# DM3390_CAM_FFC_ESD_AUX.net
KiCad netlist of a schematic drawn in Altium Designer
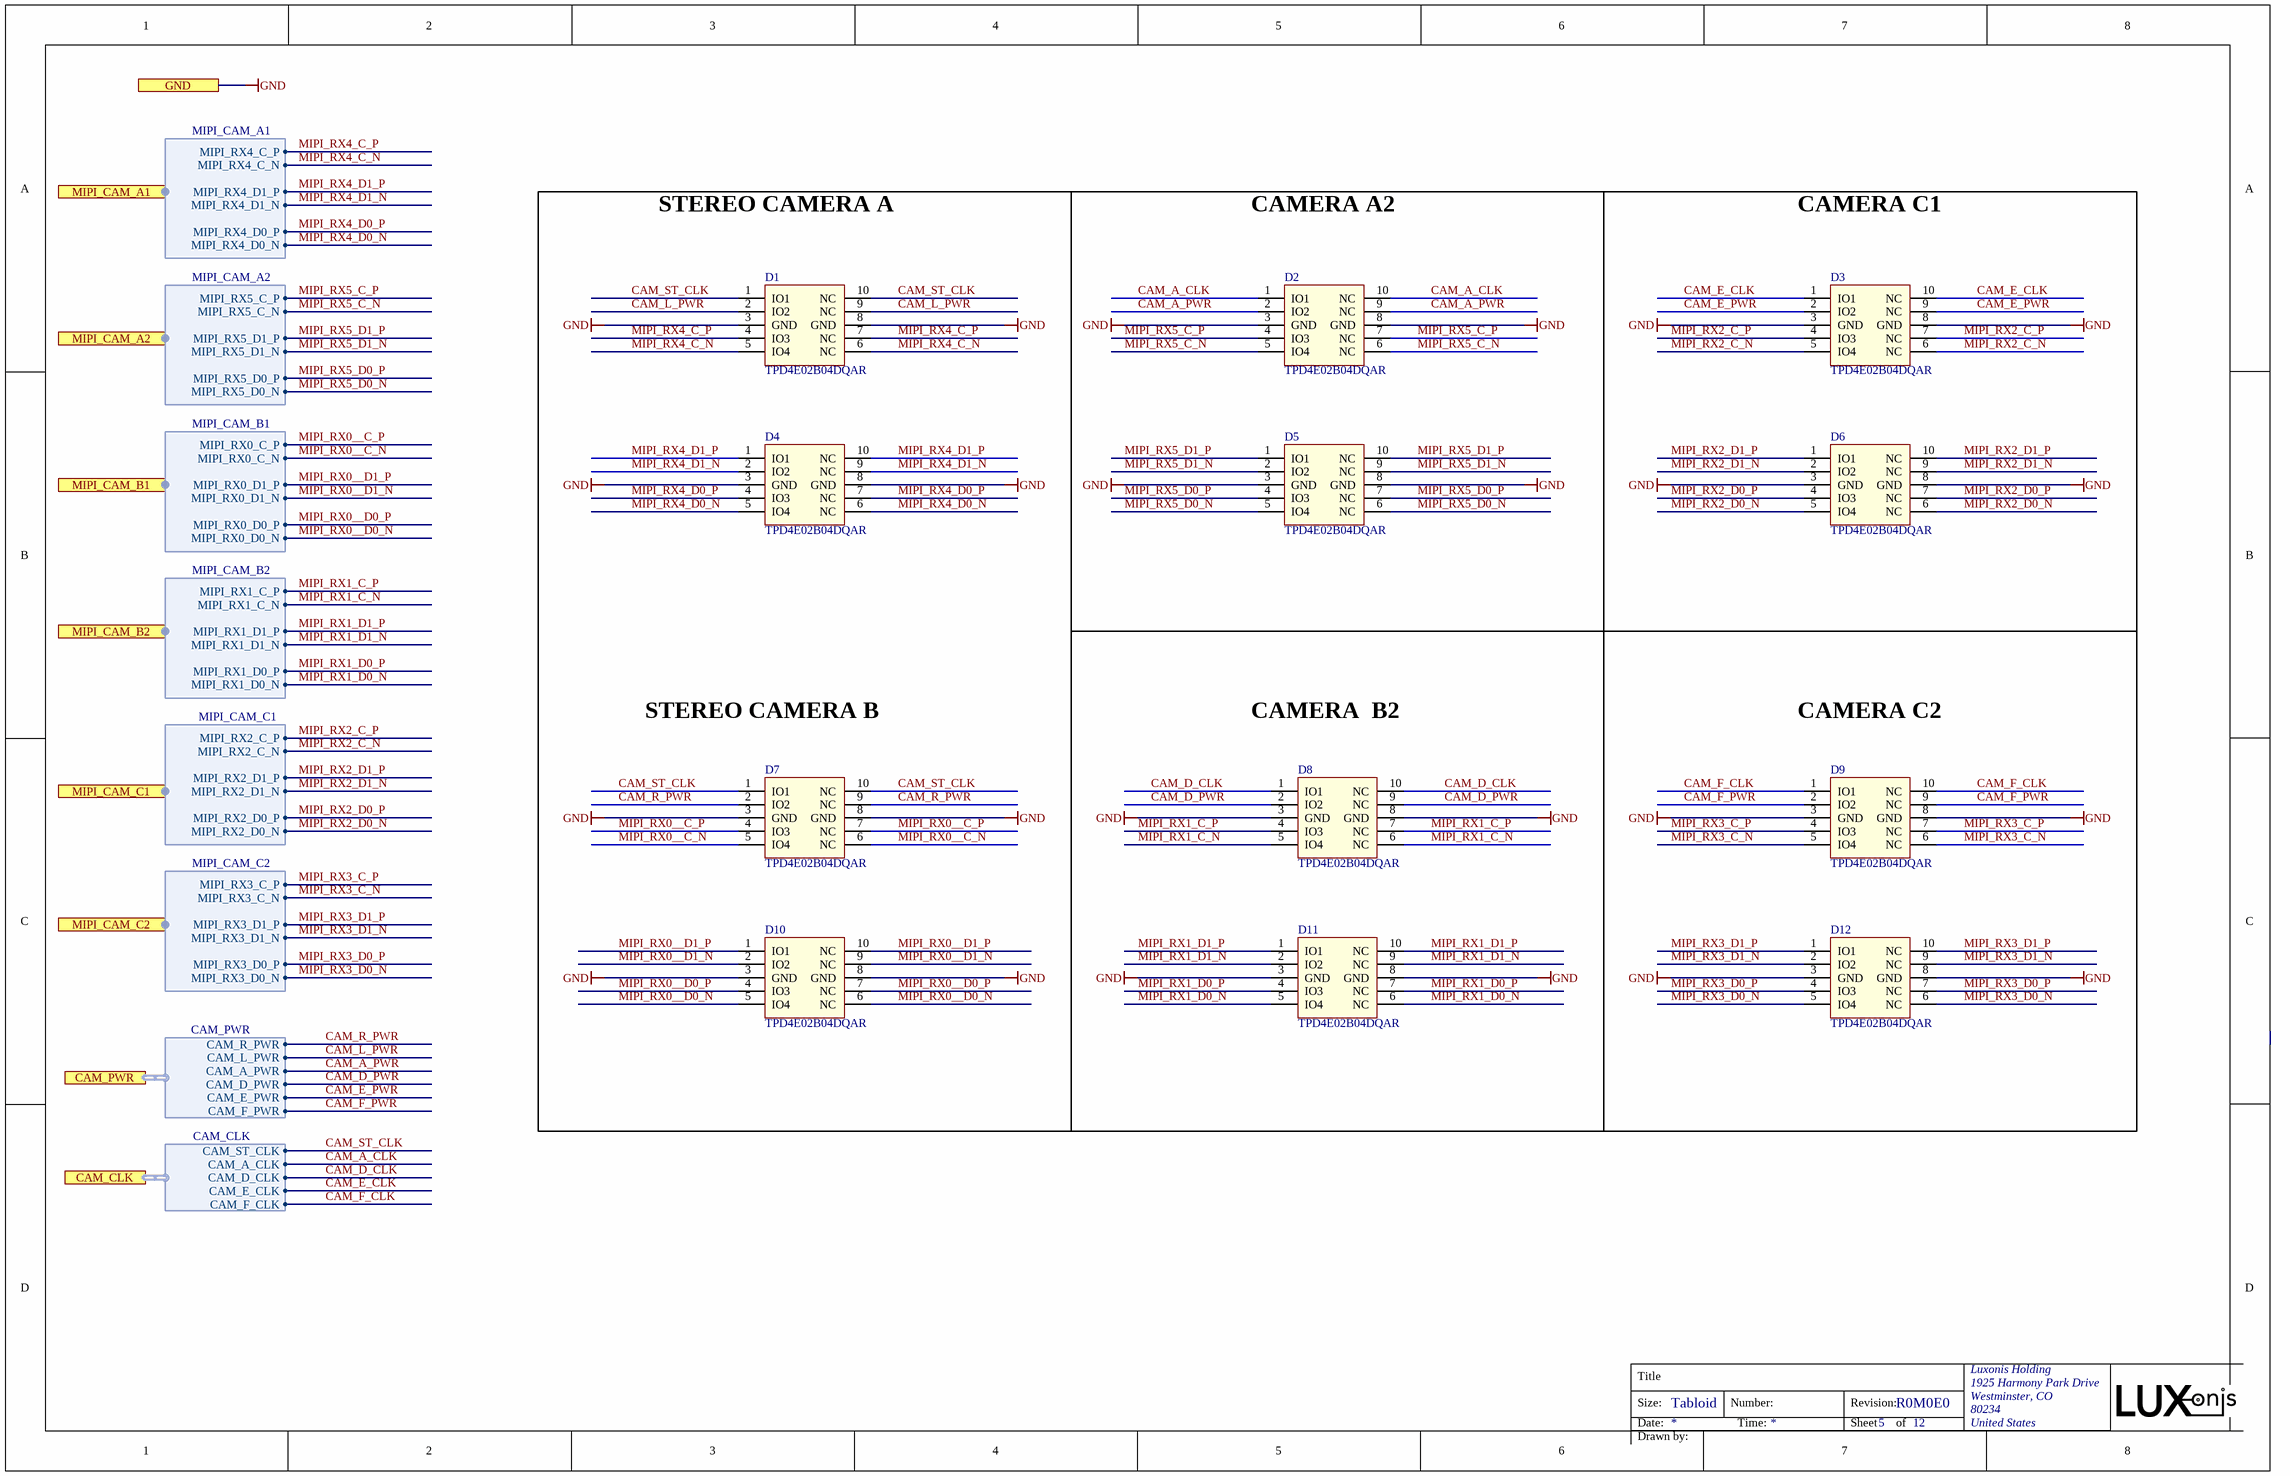
[diagram p0: DM3390_CAM_FFC_ESD_AUX.SchDoc]

(export (version "E")
  (design (tool "Eeschema 10.0.6"))
  (components
    (comp (ref "D1")
      (value "TPD4E02B04DQAR")
      (footprint "LuxonisMaster:TPD4E02B04DQAR")
      (libsource (lib "LuxonisMaster") (part "TPD4E02B04DQAR"))
    )
    (comp (ref "D2")
      (value "TPD4E02B04DQAR")
      (footprint "LuxonisMaster:TPD4E02B04DQAR")
      (libsource (lib "LuxonisMaster") (part "TPD4E02B04DQAR"))
    )
    (comp (ref "D3")
      (value "TPD4E02B04DQAR")
      (footprint "LuxonisMaster:TPD4E02B04DQAR")
      (libsource (lib "LuxonisMaster") (part "TPD4E02B04DQAR"))
    )
    (comp (ref "D4")
      (value "TPD4E02B04DQAR")
      (footprint "LuxonisMaster:TPD4E02B04DQAR")
      (libsource (lib "LuxonisMaster") (part "TPD4E02B04DQAR"))
    )
    (comp (ref "D5")
      (value "TPD4E02B04DQAR")
      (footprint "LuxonisMaster:TPD4E02B04DQAR")
      (libsource (lib "LuxonisMaster") (part "TPD4E02B04DQAR"))
    )
    (comp (ref "D6")
      (value "TPD4E02B04DQAR")
      (footprint "LuxonisMaster:TPD4E02B04DQAR")
      (libsource (lib "LuxonisMaster") (part "TPD4E02B04DQAR"))
    )
    (comp (ref "D7")
      (value "TPD4E02B04DQAR")
      (footprint "LuxonisMaster:TPD4E02B04DQAR")
      (libsource (lib "LuxonisMaster") (part "TPD4E02B04DQAR"))
    )
    (comp (ref "D8")
      (value "TPD4E02B04DQAR")
      (footprint "LuxonisMaster:TPD4E02B04DQAR")
      (libsource (lib "LuxonisMaster") (part "TPD4E02B04DQAR"))
    )
    (comp (ref "D9")
      (value "TPD4E02B04DQAR")
      (footprint "LuxonisMaster:TPD4E02B04DQAR")
      (libsource (lib "LuxonisMaster") (part "TPD4E02B04DQAR"))
    )
    (comp (ref "D10")
      (value "TPD4E02B04DQAR")
      (footprint "LuxonisMaster:TPD4E02B04DQAR")
      (libsource (lib "LuxonisMaster") (part "TPD4E02B04DQAR"))
    )
    (comp (ref "D11")
      (value "TPD4E02B04DQAR")
      (footprint "LuxonisMaster:TPD4E02B04DQAR")
      (libsource (lib "LuxonisMaster") (part "TPD4E02B04DQAR"))
    )
    (comp (ref "D12")
      (value "TPD4E02B04DQAR")
      (footprint "LuxonisMaster:TPD4E02B04DQAR")
      (libsource (lib "LuxonisMaster") (part "TPD4E02B04DQAR"))
    )
  )
  (nets
    (net (code "9") (name "/CAM_A_CLK") (class "Default")
      (node (ref "D2") (pin "1") (pinfunction "IO1_1") (pintype "passive"))
      (node (ref "D2") (pin "10") (pinfunction "NC_10") (pintype "passive"))
    )
    (net (code "10") (name "/CAM_A_PWR") (class "Default")
      (node (ref "D2") (pin "2") (pinfunction "IO2_2") (pintype "passive"))
      (node (ref "D2") (pin "9") (pinfunction "NC_9") (pintype "passive"))
    )
    (net (code "11") (name "/CAM_D_CLK") (class "Default")
      (node (ref "D8") (pin "1") (pinfunction "IO1_1") (pintype "passive"))
      (node (ref "D8") (pin "10") (pinfunction "NC_10") (pintype "passive"))
    )
    (net (code "12") (name "/CAM_D_PWR") (class "Default")
      (node (ref "D8") (pin "2") (pinfunction "IO2_2") (pintype "passive"))
      (node (ref "D8") (pin "9") (pinfunction "NC_9") (pintype "passive"))
    )
    (net (code "13") (name "/CAM_E_CLK") (class "Default")
      (node (ref "D3") (pin "1") (pinfunction "IO1_1") (pintype "passive"))
      (node (ref "D3") (pin "10") (pinfunction "NC_10") (pintype "passive"))
    )
    (net (code "14") (name "/CAM_E_PWR") (class "Default")
      (node (ref "D3") (pin "2") (pinfunction "IO2_2") (pintype "passive"))
      (node (ref "D3") (pin "9") (pinfunction "NC_9") (pintype "passive"))
    )
    (net (code "15") (name "/CAM_F_CLK") (class "Default")
      (node (ref "D9") (pin "1") (pinfunction "IO1_1") (pintype "passive"))
      (node (ref "D9") (pin "10") (pinfunction "NC_10") (pintype "passive"))
    )
    (net (code "16") (name "/CAM_F_PWR") (class "Default")
      (node (ref "D9") (pin "2") (pinfunction "IO2_2") (pintype "passive"))
      (node (ref "D9") (pin "9") (pinfunction "NC_9") (pintype "passive"))
    )
    (net (code "17") (name "/CAM_L_PWR") (class "Default")
      (node (ref "D1") (pin "2") (pinfunction "IO2_2") (pintype "passive"))
      (node (ref "D1") (pin "9") (pinfunction "NC_9") (pintype "passive"))
    )
    (net (code "18") (name "/CAM_R_PWR") (class "Default")
      (node (ref "D7") (pin "2") (pinfunction "IO2_2") (pintype "passive"))
      (node (ref "D7") (pin "9") (pinfunction "NC_9") (pintype "passive"))
    )
    (net (code "19") (name "/CAM_ST_CLK") (class "Default")
      (node (ref "D1") (pin "1") (pinfunction "IO1_1") (pintype "passive"))
      (node (ref "D1") (pin "10") (pinfunction "NC_10") (pintype "passive"))
      (node (ref "D7") (pin "1") (pinfunction "IO1_1") (pintype "passive"))
      (node (ref "D7") (pin "10") (pinfunction "NC_10") (pintype "passive"))
    )
    (net (code "20") (name "/MIPI_RX0__C_N") (class "Default")
      (node (ref "D7") (pin "5") (pinfunction "IO4_5") (pintype "passive"))
      (node (ref "D7") (pin "6") (pinfunction "NC_6") (pintype "passive"))
    )
    (net (code "21") (name "/MIPI_RX0__C_P") (class "Default")
      (node (ref "D7") (pin "4") (pinfunction "IO3_4") (pintype "passive"))
      (node (ref "D7") (pin "7") (pinfunction "NC_7") (pintype "passive"))
    )
    (net (code "22") (name "/MIPI_RX0__D0_N") (class "Default")
      (node (ref "D10") (pin "5") (pinfunction "IO4_5") (pintype "passive"))
      (node (ref "D10") (pin "6") (pinfunction "NC_6") (pintype "passive"))
    )
    (net (code "23") (name "/MIPI_RX0__D0_P") (class "Default")
      (node (ref "D10") (pin "4") (pinfunction "IO3_4") (pintype "passive"))
      (node (ref "D10") (pin "7") (pinfunction "NC_7") (pintype "passive"))
    )
    (net (code "24") (name "/MIPI_RX0__D1_N") (class "Default")
      (node (ref "D10") (pin "2") (pinfunction "IO2_2") (pintype "passive"))
      (node (ref "D10") (pin "9") (pinfunction "NC_9") (pintype "passive"))
    )
    (net (code "25") (name "/MIPI_RX0__D1_P") (class "Default")
      (node (ref "D10") (pin "1") (pinfunction "IO1_1") (pintype "passive"))
      (node (ref "D10") (pin "10") (pinfunction "NC_10") (pintype "passive"))
    )
    (net (code "26") (name "/MIPI_RX1_C_N") (class "Default")
      (node (ref "D8") (pin "5") (pinfunction "IO4_5") (pintype "passive"))
      (node (ref "D8") (pin "6") (pinfunction "NC_6") (pintype "passive"))
    )
    (net (code "27") (name "/MIPI_RX1_C_P") (class "Default")
      (node (ref "D8") (pin "4") (pinfunction "IO3_4") (pintype "passive"))
      (node (ref "D8") (pin "7") (pinfunction "NC_7") (pintype "passive"))
    )
    (net (code "28") (name "/MIPI_RX1_D0_N") (class "Default")
      (node (ref "D11") (pin "5") (pinfunction "IO4_5") (pintype "passive"))
      (node (ref "D11") (pin "6") (pinfunction "NC_6") (pintype "passive"))
    )
    (net (code "29") (name "/MIPI_RX1_D0_P") (class "Default")
      (node (ref "D11") (pin "4") (pinfunction "IO3_4") (pintype "passive"))
      (node (ref "D11") (pin "7") (pinfunction "NC_7") (pintype "passive"))
    )
    (net (code "30") (name "/MIPI_RX1_D1_N") (class "Default")
      (node (ref "D11") (pin "2") (pinfunction "IO2_2") (pintype "passive"))
      (node (ref "D11") (pin "9") (pinfunction "NC_9") (pintype "passive"))
    )
    (net (code "31") (name "/MIPI_RX1_D1_P") (class "Default")
      (node (ref "D11") (pin "1") (pinfunction "IO1_1") (pintype "passive"))
      (node (ref "D11") (pin "10") (pinfunction "NC_10") (pintype "passive"))
    )
    (net (code "32") (name "/MIPI_RX2_C_N") (class "Default")
      (node (ref "D3") (pin "5") (pinfunction "IO4_5") (pintype "passive"))
      (node (ref "D3") (pin "6") (pinfunction "NC_6") (pintype "passive"))
    )
    (net (code "33") (name "/MIPI_RX2_C_P") (class "Default")
      (node (ref "D3") (pin "4") (pinfunction "IO3_4") (pintype "passive"))
      (node (ref "D3") (pin "7") (pinfunction "NC_7") (pintype "passive"))
    )
    (net (code "34") (name "/MIPI_RX2_D0_N") (class "Default")
      (node (ref "D6") (pin "5") (pinfunction "IO4_5") (pintype "passive"))
      (node (ref "D6") (pin "6") (pinfunction "NC_6") (pintype "passive"))
    )
    (net (code "35") (name "/MIPI_RX2_D0_P") (class "Default")
      (node (ref "D6") (pin "4") (pinfunction "IO3_4") (pintype "passive"))
      (node (ref "D6") (pin "7") (pinfunction "NC_7") (pintype "passive"))
    )
    (net (code "36") (name "/MIPI_RX2_D1_N") (class "Default")
      (node (ref "D6") (pin "2") (pinfunction "IO2_2") (pintype "passive"))
      (node (ref "D6") (pin "9") (pinfunction "NC_9") (pintype "passive"))
    )
    (net (code "37") (name "/MIPI_RX2_D1_P") (class "Default")
      (node (ref "D6") (pin "1") (pinfunction "IO1_1") (pintype "passive"))
      (node (ref "D6") (pin "10") (pinfunction "NC_10") (pintype "passive"))
    )
    (net (code "38") (name "/MIPI_RX3_C_N") (class "Default")
      (node (ref "D9") (pin "5") (pinfunction "IO4_5") (pintype "passive"))
      (node (ref "D9") (pin "6") (pinfunction "NC_6") (pintype "passive"))
    )
    (net (code "39") (name "/MIPI_RX3_C_P") (class "Default")
      (node (ref "D9") (pin "4") (pinfunction "IO3_4") (pintype "passive"))
      (node (ref "D9") (pin "7") (pinfunction "NC_7") (pintype "passive"))
    )
    (net (code "40") (name "/MIPI_RX3_D0_N") (class "Default")
      (node (ref "D12") (pin "5") (pinfunction "IO4_5") (pintype "passive"))
      (node (ref "D12") (pin "6") (pinfunction "NC_6") (pintype "passive"))
    )
    (net (code "41") (name "/MIPI_RX3_D0_P") (class "Default")
      (node (ref "D12") (pin "4") (pinfunction "IO3_4") (pintype "passive"))
      (node (ref "D12") (pin "7") (pinfunction "NC_7") (pintype "passive"))
    )
    (net (code "42") (name "/MIPI_RX3_D1_N") (class "Default")
      (node (ref "D12") (pin "2") (pinfunction "IO2_2") (pintype "passive"))
      (node (ref "D12") (pin "9") (pinfunction "NC_9") (pintype "passive"))
    )
    (net (code "43") (name "/MIPI_RX3_D1_P") (class "Default")
      (node (ref "D12") (pin "1") (pinfunction "IO1_1") (pintype "passive"))
      (node (ref "D12") (pin "10") (pinfunction "NC_10") (pintype "passive"))
    )
    (net (code "44") (name "/MIPI_RX4_C_N") (class "Default")
      (node (ref "D1") (pin "5") (pinfunction "IO4_5") (pintype "passive"))
      (node (ref "D1") (pin "6") (pinfunction "NC_6") (pintype "passive"))
    )
    (net (code "45") (name "/MIPI_RX4_C_P") (class "Default")
      (node (ref "D1") (pin "4") (pinfunction "IO3_4") (pintype "passive"))
      (node (ref "D1") (pin "7") (pinfunction "NC_7") (pintype "passive"))
    )
    (net (code "46") (name "/MIPI_RX4_D0_N") (class "Default")
      (node (ref "D4") (pin "5") (pinfunction "IO4_5") (pintype "passive"))
      (node (ref "D4") (pin "6") (pinfunction "NC_6") (pintype "passive"))
    )
    (net (code "47") (name "/MIPI_RX4_D0_P") (class "Default")
      (node (ref "D4") (pin "4") (pinfunction "IO3_4") (pintype "passive"))
      (node (ref "D4") (pin "7") (pinfunction "NC_7") (pintype "passive"))
    )
    (net (code "48") (name "/MIPI_RX4_D1_N") (class "Default")
      (node (ref "D4") (pin "2") (pinfunction "IO2_2") (pintype "passive"))
      (node (ref "D4") (pin "9") (pinfunction "NC_9") (pintype "passive"))
    )
    (net (code "49") (name "/MIPI_RX4_D1_P") (class "Default")
      (node (ref "D4") (pin "1") (pinfunction "IO1_1") (pintype "passive"))
      (node (ref "D4") (pin "10") (pinfunction "NC_10") (pintype "passive"))
    )
    (net (code "50") (name "/MIPI_RX5_C_N") (class "Default")
      (node (ref "D2") (pin "5") (pinfunction "IO4_5") (pintype "passive"))
      (node (ref "D2") (pin "6") (pinfunction "NC_6") (pintype "passive"))
    )
    (net (code "51") (name "/MIPI_RX5_C_P") (class "Default")
      (node (ref "D2") (pin "4") (pinfunction "IO3_4") (pintype "passive"))
      (node (ref "D2") (pin "7") (pinfunction "NC_7") (pintype "passive"))
    )
    (net (code "52") (name "/MIPI_RX5_D0_N") (class "Default")
      (node (ref "D5") (pin "5") (pinfunction "IO4_5") (pintype "passive"))
      (node (ref "D5") (pin "6") (pinfunction "NC_6") (pintype "passive"))
    )
    (net (code "53") (name "/MIPI_RX5_D0_P") (class "Default")
      (node (ref "D5") (pin "4") (pinfunction "IO3_4") (pintype "passive"))
      (node (ref "D5") (pin "7") (pinfunction "NC_7") (pintype "passive"))
    )
    (net (code "54") (name "/MIPI_RX5_D1_N") (class "Default")
      (node (ref "D5") (pin "2") (pinfunction "IO2_2") (pintype "passive"))
      (node (ref "D5") (pin "9") (pinfunction "NC_9") (pintype "passive"))
    )
    (net (code "55") (name "/MIPI_RX5_D1_P") (class "Default")
      (node (ref "D5") (pin "1") (pinfunction "IO1_1") (pintype "passive"))
      (node (ref "D5") (pin "10") (pinfunction "NC_10") (pintype "passive"))
    )
    (net (code "64") (name "GND") (class "Default")
      (node (ref "D1") (pin "3") (pinfunction "GND_3") (pintype "passive"))
      (node (ref "D1") (pin "8") (pinfunction "GND_8") (pintype "passive"))
      (node (ref "D10") (pin "3") (pinfunction "GND_3") (pintype "passive"))
      (node (ref "D10") (pin "8") (pinfunction "GND_8") (pintype "passive"))
      (node (ref "D11") (pin "3") (pinfunction "GND_3") (pintype "passive"))
      (node (ref "D11") (pin "8") (pinfunction "GND_8") (pintype "passive"))
      (node (ref "D12") (pin "3") (pinfunction "GND_3") (pintype "passive"))
      (node (ref "D12") (pin "8") (pinfunction "GND_8") (pintype "passive"))
      (node (ref "D2") (pin "3") (pinfunction "GND_3") (pintype "passive"))
      (node (ref "D2") (pin "8") (pinfunction "GND_8") (pintype "passive"))
      (node (ref "D3") (pin "3") (pinfunction "GND_3") (pintype "passive"))
      (node (ref "D3") (pin "8") (pinfunction "GND_8") (pintype "passive"))
      (node (ref "D4") (pin "3") (pinfunction "GND_3") (pintype "passive"))
      (node (ref "D4") (pin "8") (pinfunction "GND_8") (pintype "passive"))
      (node (ref "D5") (pin "3") (pinfunction "GND_3") (pintype "passive"))
      (node (ref "D5") (pin "8") (pinfunction "GND_8") (pintype "passive"))
      (node (ref "D6") (pin "3") (pinfunction "GND_3") (pintype "passive"))
      (node (ref "D6") (pin "8") (pinfunction "GND_8") (pintype "passive"))
      (node (ref "D7") (pin "3") (pinfunction "GND_3") (pintype "passive"))
      (node (ref "D7") (pin "8") (pinfunction "GND_8") (pintype "passive"))
      (node (ref "D8") (pin "3") (pinfunction "GND_3") (pintype "passive"))
      (node (ref "D8") (pin "8") (pinfunction "GND_8") (pintype "passive"))
      (node (ref "D9") (pin "3") (pinfunction "GND_3") (pintype "passive"))
      (node (ref "D9") (pin "8") (pinfunction "GND_8") (pintype "passive"))
    )
  )
)
